# Sensor.net
KiCad netlist of a schematic drawn in Altium Designer
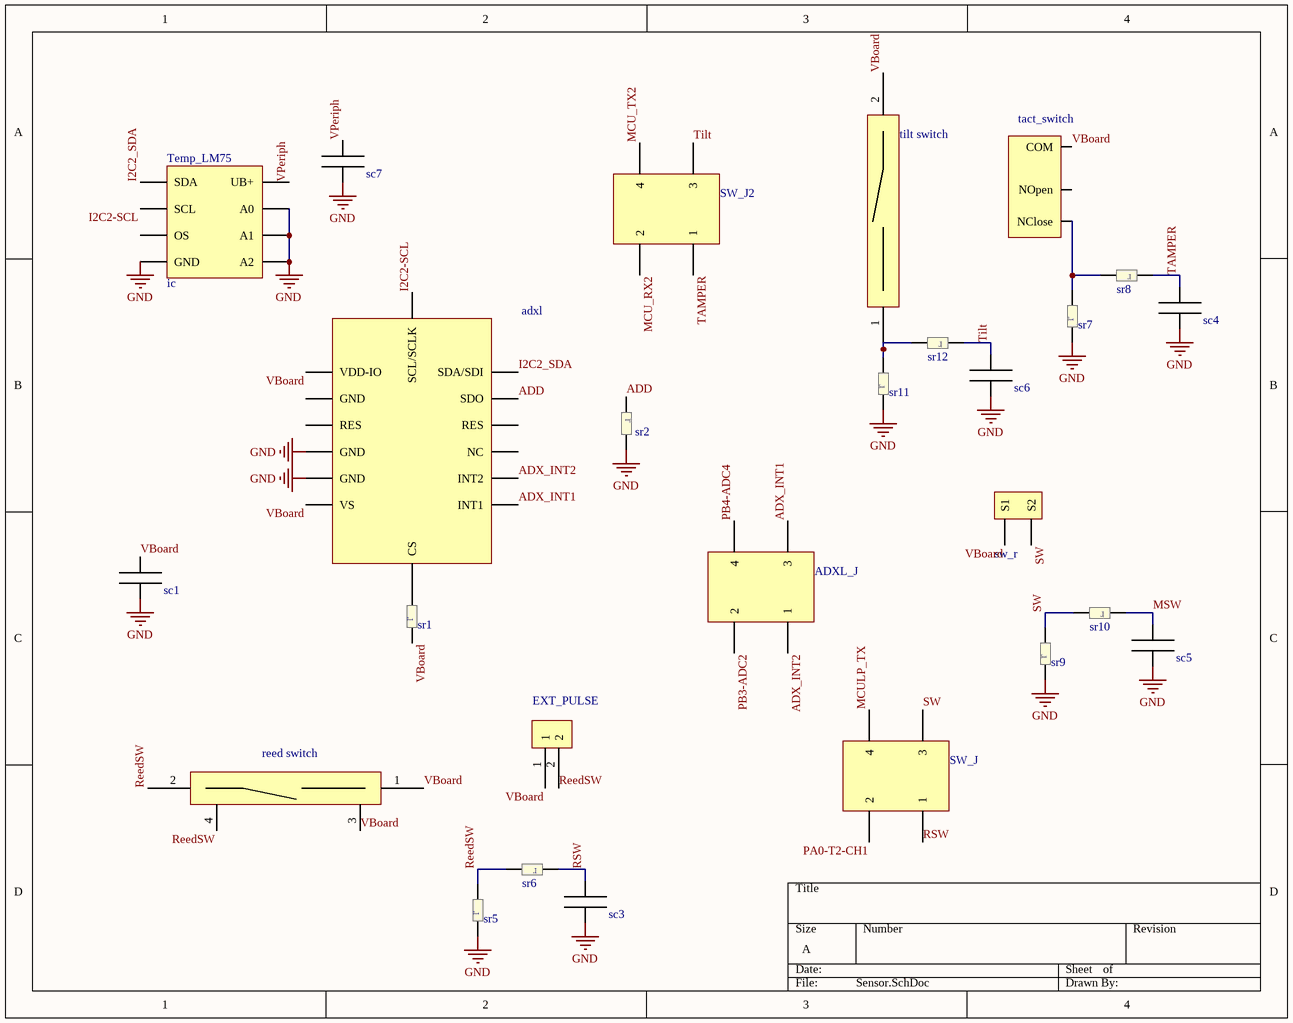
[diagram p0: Sensor.SchDoc]

(export (version "E")
  (design (tool "Eeschema 10.0.6"))
  (components
    (comp (ref "adxl")
      (value "ic")
      (footprint "abr_ic_adxl345_3d")
      (libsource (lib "abr_ic") (part "abr_ic_adxl345"))
    )
    (comp (ref "ADXL_J")
      (value "pin header 2mm")
      (footprint "abr_ph_2x2_2mm_3d_male")
      (libsource (lib "abr_ph_2mm_96_02") (part "abr_2x2_2mm"))
    )
    (comp (ref "EXT_PULSE")
      (value "YB2 SMD")
      (footprint "abr_sw_yb_2p_3d")
      (libsource (lib "lpwireless") (part "YB2 SMD"))
    )
    (comp (ref "reed switch")
      (value "switch")
      (footprint "abr_reed_sw_3d")
      (libsource (lib "abr_switch") (part "abr_reed_sw"))
    )
    (comp (ref "sc1")
      (value "100nf")
      (footprint "abr_cap_0805_3d")
      (libsource (lib "abr_smd_0805_all") (part "abr_cap_0805"))
    )
    (comp (ref "sc3")
      (value "100nf")
      (footprint "abr_cap_0805_3d")
      (libsource (lib "abr_smd_0805_all") (part "abr_cap_0805"))
    )
    (comp (ref "sc4")
      (value "100nf")
      (footprint "abr_cap_0805_3d")
      (libsource (lib "abr_smd_0805_all") (part "abr_cap_0805"))
    )
    (comp (ref "sc5")
      (value "100nf")
      (footprint "abr_cap_0805_3d")
      (libsource (lib "abr_smd_0805_all") (part "abr_cap_0805"))
    )
    (comp (ref "sc6")
      (value "100nf")
      (footprint "abr_cap_0805_3d")
      (libsource (lib "abr_smd_0805_all") (part "abr_cap_0805"))
    )
    (comp (ref "sc7")
      (value "100nf")
      (footprint "abr_cap_0805_3d")
      (libsource (lib "abr_smd_0805_all") (part "abr_cap_0805"))
    )
    (comp (ref "sr1")
      (value "100k")
      (footprint "abr_res_0805_3d")
      (libsource (lib "") (part "abr_res_0805_1"))
    )
    (comp (ref "sr2")
      (value "100k")
      (footprint "abr_res_0805_3d")
      (libsource (lib "") (part "abr_res_0805_2"))
    )
    (comp (ref "sr5")
      (value "2.2K")
      (footprint "abr_res_0805_3d")
      (libsource (lib "") (part "abr_res_0805_1"))
    )
    (comp (ref "sr6")
      (value "1k")
      (footprint "abr_res_0805_3d")
      (libsource (lib "abr_smd_0805_all") (part "abr_res_0805"))
    )
    (comp (ref "sr7")
      (value "2.2K")
      (footprint "abr_res_0805_3d")
      (libsource (lib "") (part "abr_res_0805_1"))
    )
    (comp (ref "sr8")
      (value "1k")
      (footprint "abr_res_0805_3d")
      (libsource (lib "abr_smd_0805_all") (part "abr_res_0805"))
    )
    (comp (ref "sr9")
      (value "2.2K")
      (footprint "abr_res_0805_3d")
      (libsource (lib "") (part "abr_res_0805_1"))
    )
    (comp (ref "sr10")
      (value "1k")
      (footprint "abr_res_0805_3d")
      (libsource (lib "abr_smd_0805_all") (part "abr_res_0805"))
    )
    (comp (ref "sr11")
      (value "2.2K")
      (footprint "abr_res_0805_3d")
      (libsource (lib "") (part "abr_res_0805_1"))
    )
    (comp (ref "sr12")
      (value "1k")
      (footprint "abr_res_0805_3d")
      (libsource (lib "abr_smd_0805_all") (part "abr_res_0805"))
    )
    (comp (ref "SW_J")
      (value "pin header 2mm")
      (footprint "abr_ph_2x2_2mm_3d_male")
      (libsource (lib "abr_ph_2mm_96_02") (part "abr_2x2_2mm"))
    )
    (comp (ref "SW_J2")
      (value "pin header 2mm")
      (footprint "abr_ph_2x2_2mm_3d_male")
      (libsource (lib "abr_ph_2mm_96_02") (part "abr_2x2_2mm"))
    )
    (comp (ref "sw_r")
      (value "switch")
      (footprint "abr_sw_tact_3d")
      (libsource (lib "abr_switch") (part "abr_switch_tact"))
    )
    (comp (ref "tact_switch")
      (value "switch")
      (footprint "abr_proximity_switch_3d")
      (libsource (lib "abr_switch") (part "abr_tact_switch"))
    )
    (comp (ref "Temp_LM75")
      (value "ic")
      (footprint "abr_ic_lm75_3d")
      (libsource (lib "abr_ic") (part "abr_ic_lm75"))
    )
    (comp (ref "tilt switch")
      (value "switch")
      (footprint "abr_tilt_horiz_sw200d_3d")
      (libsource (lib "abr_switch") (part "abr_tilt_sw"))
    )
  )
  (nets
    (net (code "1") (name "/ADD") (class "Default")
      (node (ref "adxl") (pin "12") (pinfunction "SDO_12") (pintype "passive"))
      (node (ref "sr2") (pin "0") (pinfunction "0_0") (pintype "passive"))
    )
    (net (code "2") (name "/ADX_INT1") (class "Default")
      (node (ref "ADXL_J") (pin "3") (pinfunction "3_3") (pintype "passive"))
      (node (ref "adxl") (pin "8") (pinfunction "INT1_8") (pintype "passive"))
    )
    (net (code "3") (name "/ADX_INT2") (class "Default")
      (node (ref "ADXL_J") (pin "1") (pinfunction "1_1") (pintype "passive"))
      (node (ref "adxl") (pin "9") (pinfunction "INT2_9") (pintype "passive"))
    )
    (net (code "4") (name "/I2C2-SCL") (class "Default")
      (node (ref "Temp_LM75") (pin "2") (pinfunction "SCL_2") (pintype "passive"))
      (node (ref "adxl") (pin "14") (pinfunction "SCL/SCLK_14") (pintype "passive"))
    )
    (net (code "5") (name "/I2C2_SDA") (class "Default")
      (node (ref "Temp_LM75") (pin "1") (pinfunction "SDA_1") (pintype "passive"))
      (node (ref "adxl") (pin "13") (pinfunction "SDA/SDI_13") (pintype "passive"))
    )
    (net (code "6") (name "/MCULP_TX") (class "Default")
      (node (ref "SW_J") (pin "4") (pinfunction "4_4") (pintype "passive"))
    )
    (net (code "7") (name "/MCU_RX2") (class "Default")
      (node (ref "SW_J2") (pin "2") (pinfunction "2_2") (pintype "passive"))
    )
    (net (code "8") (name "/MCU_TX2") (class "Default")
      (node (ref "SW_J2") (pin "4") (pinfunction "4_4") (pintype "passive"))
    )
    (net (code "9") (name "/MSW") (class "Default")
      (node (ref "sc5") (pin "1") (pinfunction "10_1") (pintype "passive"))
      (node (ref "sr10") (pin "0") (pinfunction "0_0") (pintype "passive"))
    )
    (net (code "10") (name "/PA0-T2-CH1") (class "Default")
      (node (ref "SW_J") (pin "2") (pinfunction "2_2") (pintype "passive"))
    )
    (net (code "11") (name "/PB3-ADC2") (class "Default")
      (node (ref "ADXL_J") (pin "2") (pinfunction "2_2") (pintype "passive"))
    )
    (net (code "12") (name "/PB4-ADC4") (class "Default")
      (node (ref "ADXL_J") (pin "4") (pinfunction "4_4") (pintype "passive"))
    )
    (net (code "13") (name "/RSW") (class "Default")
      (node (ref "SW_J") (pin "1") (pinfunction "1_1") (pintype "passive"))
      (node (ref "sc3") (pin "1") (pinfunction "10_1") (pintype "passive"))
      (node (ref "sr6") (pin "0") (pinfunction "0_0") (pintype "passive"))
    )
    (net (code "14") (name "/ReedSW") (class "Default")
      (node (ref "EXT_PULSE") (pin "2") (pinfunction "2_2") (pintype "passive"))
      (node (ref "reed switch") (pin "2") (pintype "passive"))
      (node (ref "reed switch") (pin "4") (pintype "passive"))
      (node (ref "sr5") (pin "1") (pinfunction "0_1") (pintype "passive"))
      (node (ref "sr6") (pin "1") (pinfunction "0_1") (pintype "passive"))
    )
    (net (code "15") (name "/SW") (class "Default")
      (node (ref "SW_J") (pin "3") (pinfunction "3_3") (pintype "passive"))
      (node (ref "sr10") (pin "1") (pinfunction "0_1") (pintype "passive"))
      (node (ref "sr9") (pin "1") (pinfunction "0_1") (pintype "passive"))
      (node (ref "sw_r") (pin "2") (pinfunction "S2_2") (pintype "passive"))
    )
    (net (code "16") (name "/TAMPER") (class "Default")
      (node (ref "SW_J2") (pin "1") (pinfunction "1_1") (pintype "passive"))
      (node (ref "sc4") (pin "1") (pinfunction "10_1") (pintype "passive"))
      (node (ref "sr8") (pin "0") (pinfunction "0_0") (pintype "passive"))
    )
    (net (code "17") (name "/Tilt") (class "Default")
      (node (ref "SW_J2") (pin "3") (pinfunction "3_3") (pintype "passive"))
      (node (ref "sc6") (pin "1") (pinfunction "10_1") (pintype "passive"))
      (node (ref "sr12") (pin "0") (pinfunction "0_0") (pintype "passive"))
    )
    (net (code "18") (name "/VBoard") (class "Default")
      (node (ref "EXT_PULSE") (pin "1") (pinfunction "1_1") (pintype "passive"))
      (node (ref "adxl") (pin "1") (pinfunction "VDD-IO_1") (pintype "passive"))
      (node (ref "adxl") (pin "6") (pinfunction "VS_6") (pintype "passive"))
      (node (ref "reed switch") (pin "1") (pintype "passive"))
      (node (ref "reed switch") (pin "3") (pintype "passive"))
      (node (ref "sc1") (pin "1") (pinfunction "10_1") (pintype "passive"))
      (node (ref "sr1") (pin "0") (pinfunction "0_0") (pintype "passive"))
      (node (ref "sw_r") (pin "1") (pinfunction "S1_1") (pintype "passive"))
      (node (ref "tact_switch") (pin "1") (pinfunction "COM_1") (pintype "passive"))
      (node (ref "tilt switch") (pin "2") (pintype "passive"))
    )
    (net (code "19") (name "/VPeriph") (class "Default")
      (node (ref "Temp_LM75") (pin "8") (pinfunction "UB+_8") (pintype "passive"))
      (node (ref "sc7") (pin "0") (pinfunction "2_0") (pintype "passive"))
    )
    (net (code "20") (name "GND") (class "Default")
      (node (ref "Temp_LM75") (pin "4") (pinfunction "GND_4") (pintype "passive"))
      (node (ref "Temp_LM75") (pin "5") (pinfunction "A2_5") (pintype "passive"))
      (node (ref "Temp_LM75") (pin "6") (pinfunction "A1_6") (pintype "passive"))
      (node (ref "Temp_LM75") (pin "7") (pinfunction "A0_7") (pintype "passive"))
      (node (ref "adxl") (pin "4") (pinfunction "GND_4") (pintype "passive"))
      (node (ref "adxl") (pin "5") (pinfunction "GND_5") (pintype "passive"))
      (node (ref "sc1") (pin "0") (pinfunction "2_0") (pintype "passive"))
      (node (ref "sc3") (pin "0") (pinfunction "2_0") (pintype "passive"))
      (node (ref "sc4") (pin "0") (pinfunction "2_0") (pintype "passive"))
      (node (ref "sc5") (pin "0") (pinfunction "2_0") (pintype "passive"))
      (node (ref "sc6") (pin "0") (pinfunction "2_0") (pintype "passive"))
      (node (ref "sc7") (pin "1") (pinfunction "10_1") (pintype "passive"))
      (node (ref "sr11") (pin "0") (pinfunction "0_0") (pintype "passive"))
      (node (ref "sr2") (pin "1") (pinfunction "0_1") (pintype "passive"))
      (node (ref "sr5") (pin "0") (pinfunction "0_0") (pintype "passive"))
      (node (ref "sr7") (pin "0") (pinfunction "0_0") (pintype "passive"))
      (node (ref "sr9") (pin "0") (pinfunction "0_0") (pintype "passive"))
    )
    (net (code "21") (name "Net-(adxl-CS)") (class "Default")
      (node (ref "adxl") (pin "7") (pinfunction "CS_7") (pintype "passive"))
      (node (ref "sr1") (pin "1") (pinfunction "0_1") (pintype "passive"))
    )
    (net (code "22") (name "Net-(sr11-0-Pad1)") (class "Default")
      (node (ref "sr11") (pin "1") (pinfunction "0_1") (pintype "passive"))
      (node (ref "sr12") (pin "1") (pinfunction "0_1") (pintype "passive"))
      (node (ref "tilt switch") (pin "1") (pintype "passive"))
    )
    (net (code "23") (name "Net-(tact_switch-NClose)") (class "Default")
      (node (ref "sr7") (pin "1") (pinfunction "0_1") (pintype "passive"))
      (node (ref "sr8") (pin "1") (pinfunction "0_1") (pintype "passive"))
      (node (ref "tact_switch") (pin "3") (pinfunction "NClose_3") (pintype "passive"))
    )
    (net (code "24") (name "unconnected-(Temp_LM75-OS-Pad3)") (class "Default")
      (node (ref "Temp_LM75") (pin "3") (pinfunction "OS_3") (pintype "passive"))
    )
    (net (code "25") (name "unconnected-(adxl-GND-Pad2)") (class "Default")
      (node (ref "adxl") (pin "2") (pinfunction "GND_2") (pintype "passive"))
    )
    (net (code "26") (name "unconnected-(adxl-NC-Pad10)") (class "Default")
      (node (ref "adxl") (pin "10") (pinfunction "NC_10") (pintype "passive"))
    )
    (net (code "27") (name "unconnected-(adxl-RES-Pad3)") (class "Default")
      (node (ref "adxl") (pin "3") (pinfunction "RES_3") (pintype "passive"))
    )
    (net (code "28") (name "unconnected-(adxl-RES-Pad11)") (class "Default")
      (node (ref "adxl") (pin "11") (pinfunction "RES_11") (pintype "passive"))
    )
    (net (code "29") (name "unconnected-(tact_switch-NOpen-Pad2)") (class "Default")
      (node (ref "tact_switch") (pin "2") (pinfunction "NOpen_2") (pintype "passive"))
    )
  )
)
